# Peripherals.net
KiCad netlist of a schematic drawn in Altium Designer
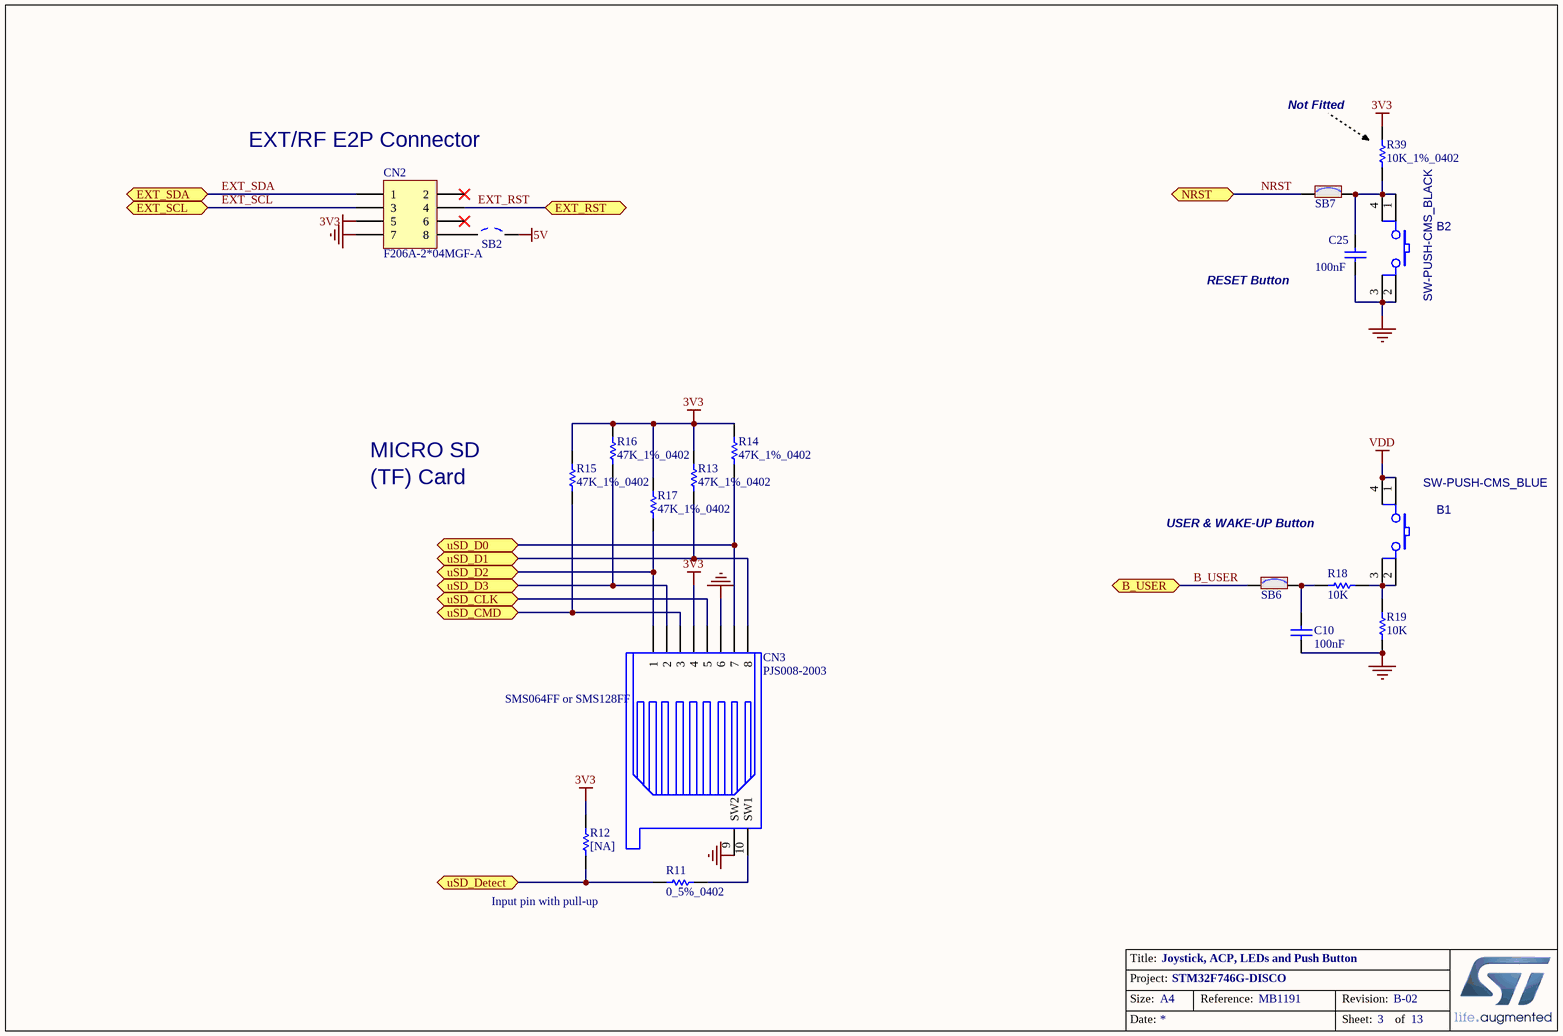
[diagram p0: Peripherals.SchDoc]

(export (version "E")
  (design (tool "Eeschema 10.0.6"))
  (components
    (comp (ref "B1")
      (value "SW-PUSH-CMS_BLUE")
      (footprint "BP1CMS")
      (description "Non-Open Push Button,Blue 0.1A 24V,Square head,6*6,SMT,180Degree,TD-0341X-GO1,wealthmetal")
      (libsource (lib "MCD_TOOLS") (part "SW-PUSH-CMS_BLUE"))
    )
    (comp (ref "B2")
      (value "SW-PUSH-CMS_BLACK")
      (footprint "BP1CMS")
      (description "Non-Open Push Button,Black 0.1A 24V,Square head,6*6,SMT,180Degree,TD-0341X-GO1,wealthmetal")
      (libsource (lib "MCD_TOOLS") (part "SW-PUSH-CMS_BLACK"))
    )
    (comp (ref "C10")
      (value "100nF")
      (footprint "0402C")
      (description "Capacitor,100nF,16V,X7R,10%,0402,YAGEO")
      (libsource (lib "MCD_TOOLS") (part "Cap_100nF_X7R_10%_0402"))
    )
    (comp (ref "C25")
      (value "100nF")
      (footprint "0402C")
      (description "Capacitor,100nF,16V,X7R,10%,0402,YAGEO")
      (libsource (lib "MCD_TOOLS") (part "Cap_100nF_X7R_10%_0402"))
    )
    (comp (ref "CN2")
      (value "F206A-2*04MGF-A")
      (footprint "SSM-104-L-DH")
      (description "Header, 5-Pins, Horizontal Dual row, female SMD")
      (libsource (lib "MCD_TOOLS") (part "F206A-2*04MGF-A"))
    )
    (comp (ref "CN3")
      (value "PJS008-2003")
      (footprint "MSD_PJS008")
      (description "Memory Card Connectors MicroSD Card Conn Revrs Mnt Push-Push")
      (libsource (lib "MCD_TOOLS") (part "microSD-PJS008-2003"))
    )
    (comp (ref "R11")
      (value "0_5%_0402")
      (footprint "0402R")
      (description "Resistor,0,0402,5%,YAGEO")
      (libsource (lib "MCD_TOOLS") (part "Res_0_5%_0402"))
    )
    (comp (ref "R12")
      (value "[NA]")
      (footprint "0402R")
      (description "Resistor,[NA],0402")
      (libsource (lib "MCD_TOOLS") (part "Res_NA_0402"))
    )
    (comp (ref "R13")
      (value "47K_1%_0402")
      (footprint "0402R")
      (description "Resistor,47K,0402,1%,YAGEO")
      (libsource (lib "MCD_TOOLS") (part "Res_47K_1%_0402"))
    )
    (comp (ref "R14")
      (value "47K_1%_0402")
      (footprint "0402R")
      (description "Resistor,47K,0402,1%,YAGEO")
      (libsource (lib "MCD_TOOLS") (part "Res_47K_1%_0402"))
    )
    (comp (ref "R15")
      (value "47K_1%_0402")
      (footprint "0402R")
      (description "Resistor,47K,0402,1%,YAGEO")
      (libsource (lib "MCD_TOOLS") (part "Res_47K_1%_0402"))
    )
    (comp (ref "R16")
      (value "47K_1%_0402")
      (footprint "0402R")
      (description "Resistor,47K,0402,1%,YAGEO")
      (libsource (lib "MCD_TOOLS") (part "Res_47K_1%_0402"))
    )
    (comp (ref "R17")
      (value "47K_1%_0402")
      (footprint "0402R")
      (description "Resistor,47K,0402,1%,YAGEO")
      (libsource (lib "MCD_TOOLS") (part "Res_47K_1%_0402"))
    )
    (comp (ref "R18")
      (value "10K")
      (footprint "0402R")
      (description "Resistor,10K,0402,1%,YAGEO")
      (libsource (lib "MCD_TOOLS") (part "Res_10K_1%_0402"))
    )
    (comp (ref "R19")
      (value "10K")
      (footprint "0402R")
      (description "Resistor,10K,0402,1%,YAGEO")
      (libsource (lib "MCD_TOOLS") (part "Res_10K_1%_0402"))
    )
    (comp (ref "R39")
      (value "10K_1%_0402")
      (footprint "0402R")
      (description "Resistor,10K,0402,1%,YAGEO")
      (libsource (lib "MCD_TOOLS") (part "Res_10K_1%_0402"))
    )
    (comp (ref "SB2")
      (value "Solder Bridge OFF")
      (footprint "JP2_SMD")
      (libsource (lib "MCD_TOOLS") (part "SB_OFF"))
    )
    (comp (ref "SB6")
      (value "Solder Bridge ON")
      (footprint "JP2_SMD")
      (libsource (lib "MCD_TOOLS") (part "SB_ON"))
    )
    (comp (ref "SB7")
      (value "Solder Bridge ON")
      (footprint "JP2_SMD")
      (libsource (lib "MCD_TOOLS") (part "SB_ON"))
    )
  )
  (nets
    (net (code "1") (name "/B_USER") (class "Default")
      (node (ref "SB6") (pin "1") (pinfunction "1_1") (pintype "passive"))
    )
    (net (code "2") (name "/EXT_RST") (class "Default")
      (node (ref "CN2") (pin "4") (pinfunction "4_4") (pintype "passive"))
    )
    (net (code "3") (name "/EXT_SCL") (class "Default")
      (node (ref "CN2") (pin "3") (pinfunction "3_3") (pintype "passive"))
    )
    (net (code "4") (name "/EXT_SDA") (class "Default")
      (node (ref "CN2") (pin "1") (pinfunction "1_1") (pintype "passive"))
    )
    (net (code "5") (name "/NRST") (class "Default")
      (node (ref "SB7") (pin "1") (pinfunction "1_1") (pintype "passive"))
    )
    (net (code "6") (name "/uSD_CLK") (class "Default")
      (node (ref "CN3") (pin "5") (pinfunction "5_5") (pintype "passive"))
    )
    (net (code "7") (name "/uSD_CMD") (class "Default")
      (node (ref "CN3") (pin "3") (pinfunction "3_3") (pintype "passive"))
      (node (ref "R15") (pin "1") (pinfunction "1_1") (pintype "passive"))
    )
    (net (code "8") (name "/uSD_D0") (class "Default")
      (node (ref "CN3") (pin "7") (pinfunction "7_7") (pintype "passive"))
      (node (ref "R14") (pin "1") (pinfunction "1_1") (pintype "passive"))
    )
    (net (code "9") (name "/uSD_D1") (class "Default")
      (node (ref "CN3") (pin "8") (pinfunction "8_8") (pintype "passive"))
      (node (ref "R13") (pin "1") (pinfunction "1_1") (pintype "passive"))
    )
    (net (code "10") (name "/uSD_D2") (class "Default")
      (node (ref "CN3") (pin "1") (pinfunction "1_1") (pintype "passive"))
      (node (ref "R17") (pin "1") (pinfunction "1_1") (pintype "passive"))
    )
    (net (code "11") (name "/uSD_D3") (class "Default")
      (node (ref "CN3") (pin "2") (pinfunction "2_2") (pintype "passive"))
      (node (ref "R16") (pin "1") (pinfunction "1_1") (pintype "passive"))
    )
    (net (code "12") (name "/uSD_Detect") (class "Default")
      (node (ref "R11") (pin "1") (pinfunction "1_1") (pintype "passive"))
      (node (ref "R12") (pin "1") (pinfunction "1_1") (pintype "passive"))
    )
    (net (code "13") (name "3V3") (class "Default")
      (node (ref "CN2") (pin "5") (pinfunction "5_5") (pintype "passive"))
      (node (ref "CN3") (pin "4") (pinfunction "4_4") (pintype "passive"))
      (node (ref "R12") (pin "2") (pinfunction "2_2") (pintype "passive"))
      (node (ref "R13") (pin "2") (pinfunction "2_2") (pintype "passive"))
      (node (ref "R14") (pin "2") (pinfunction "2_2") (pintype "passive"))
      (node (ref "R15") (pin "2") (pinfunction "2_2") (pintype "passive"))
      (node (ref "R16") (pin "2") (pinfunction "2_2") (pintype "passive"))
      (node (ref "R17") (pin "2") (pinfunction "2_2") (pintype "passive"))
      (node (ref "R39") (pin "2") (pinfunction "2_2") (pintype "passive"))
    )
    (net (code "14") (name "5V") (class "Default")
      (node (ref "SB2") (pin "2") (pinfunction "2_2") (pintype "passive"))
    )
    (net (code "15") (name "GND") (class "Default")
      (node (ref "B2") (pin "2") (pinfunction "2_2") (pintype "passive"))
      (node (ref "B2") (pin "3") (pinfunction "3_3") (pintype "passive"))
      (node (ref "C10") (pin "1") (pinfunction "1_1") (pintype "passive"))
      (node (ref "C25") (pin "1") (pinfunction "1_1") (pintype "passive"))
      (node (ref "CN2") (pin "7") (pinfunction "7_7") (pintype "passive"))
      (node (ref "CN3") (pin "6") (pinfunction "6_6") (pintype "passive"))
      (node (ref "CN3") (pin "9") (pinfunction "SW2_9") (pintype "passive"))
      (node (ref "R19") (pin "1") (pinfunction "1_1") (pintype "passive"))
    )
    (net (code "16") (name "Net-(B1-Pad2)") (class "Default")
      (node (ref "B1") (pin "2") (pinfunction "2_2") (pintype "passive"))
      (node (ref "B1") (pin "3") (pinfunction "3_3") (pintype "passive"))
      (node (ref "R18") (pin "2") (pinfunction "2_2") (pintype "passive"))
      (node (ref "R19") (pin "2") (pinfunction "2_2") (pintype "passive"))
    )
    (net (code "17") (name "Net-(B2-Pad1)") (class "Default")
      (node (ref "B2") (pin "1") (pinfunction "1_1") (pintype "passive"))
      (node (ref "B2") (pin "4") (pinfunction "4_4") (pintype "passive"))
      (node (ref "C25") (pin "2") (pinfunction "2_2") (pintype "passive"))
      (node (ref "R39") (pin "1") (pinfunction "1_1") (pintype "passive"))
      (node (ref "SB7") (pin "2") (pinfunction "2_2") (pintype "passive"))
    )
    (net (code "18") (name "Net-(C10-Pad2)") (class "Default")
      (node (ref "C10") (pin "2") (pinfunction "2_2") (pintype "passive"))
      (node (ref "R18") (pin "1") (pinfunction "1_1") (pintype "passive"))
      (node (ref "SB6") (pin "2") (pinfunction "2_2") (pintype "passive"))
    )
    (net (code "19") (name "Net-(CN2-Pad8)") (class "Default")
      (node (ref "CN2") (pin "8") (pinfunction "8_8") (pintype "passive"))
      (node (ref "SB2") (pin "1") (pinfunction "1_1") (pintype "passive"))
    )
    (net (code "20") (name "Net-(CN3-SW1)") (class "Default")
      (node (ref "CN3") (pin "10") (pinfunction "SW1_10") (pintype "passive"))
      (node (ref "R11") (pin "2") (pinfunction "2_2") (pintype "passive"))
    )
    (net (code "21") (name "VDD") (class "Default")
      (node (ref "B1") (pin "1") (pinfunction "1_1") (pintype "passive"))
      (node (ref "B1") (pin "4") (pinfunction "4_4") (pintype "passive"))
    )
    (net (code "22") (name "unconnected-(CN2-Pad2)") (class "Default")
      (node (ref "CN2") (pin "2") (pinfunction "2_2") (pintype "passive+no_connect"))
    )
    (net (code "23") (name "unconnected-(CN2-Pad6)") (class "Default")
      (node (ref "CN2") (pin "6") (pinfunction "6_6") (pintype "passive+no_connect"))
    )
  )
)
